# ArduinoMega.net
KiCad netlist of a schematic drawn in Altium Designer
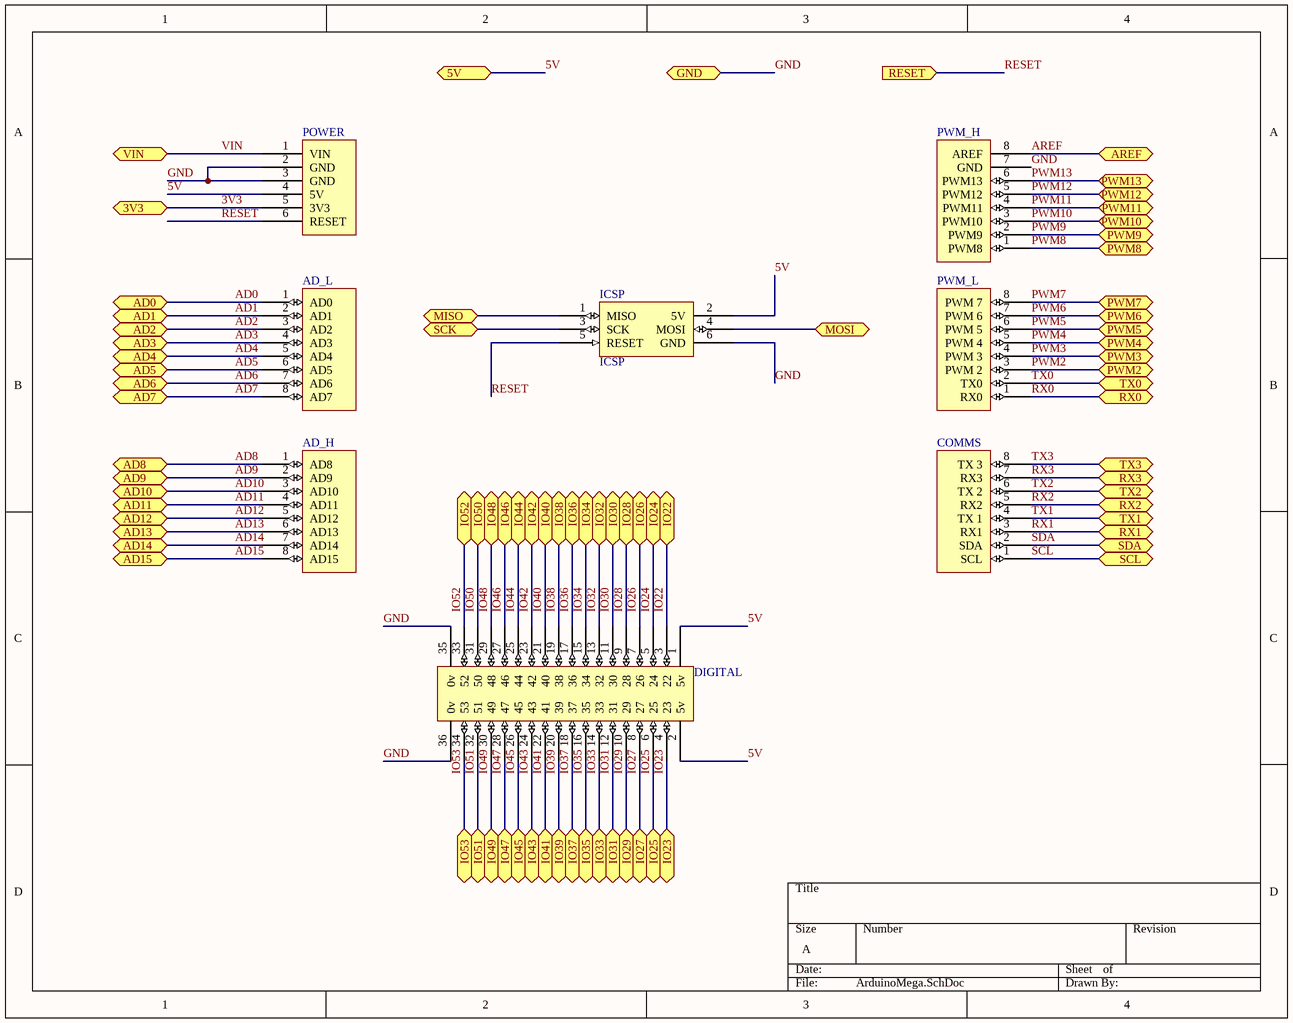
[diagram p0: ArduinoMega.SchDoc]

(export (version "E")
  (design (tool "Eeschema 10.0.6"))
  (components
    (comp (ref "AD_H") (value "AD_H") (footprint "HDR1X8") (libsource (lib "Header") (part "AD_H")))
    (comp (ref "AD_L") (value "AD_L") (footprint "HDR1X8") (libsource (lib "Header") (part "AD_L")))
    (comp (ref "COMMS")
      (value "Communication")
      (footprint "HDR1X8")
      (libsource (lib "Header") (part "Communication"))
    )
    (comp (ref "DIGITAL") (value "IO_36") (footprint "HDR2X18") (libsource (lib "Header") (part "IO_36")))
    (comp (ref "ICSP") (value "ICSP") (footprint "ICSP") (libsource (lib "Header") (part "ICSP")))
    (comp (ref "POWER") (value "POWER") (footprint "HDR1X6") (libsource (lib "Header") (part "POWER")))
    (comp (ref "PWM_H") (value "PWM_H") (footprint "HDR1X8") (libsource (lib "Header") (part "PWM_H")))
    (comp (ref "PWM_L") (value "PWM_L") (footprint "HDR1X8") (libsource (lib "Header") (part "PWM_L")))
  )
  (nets
    (net (code "1") (name "/3V3") (class "Default")
      (node (ref "POWER") (pin "5") (pinfunction "3V3_5") (pintype "power_in"))
    )
    (net (code "2") (name "/5V") (class "Default")
      (node (ref "DIGITAL") (pin "1") (pinfunction "5v_1") (pintype "power_in"))
      (node (ref "DIGITAL") (pin "2") (pinfunction "5v_2") (pintype "power_in"))
      (node (ref "ICSP") (pin "2") (pinfunction "5V_2") (pintype "power_in"))
      (node (ref "POWER") (pin "4") (pinfunction "5V_4") (pintype "power_in"))
    )
    (net (code "3") (name "/AD0") (class "Default")
      (node (ref "AD_L") (pin "1") (pinfunction "AD0_1") (pintype "bidirectional"))
    )
    (net (code "4") (name "/AD1") (class "Default")
      (node (ref "AD_L") (pin "2") (pinfunction "AD1_2") (pintype "bidirectional"))
    )
    (net (code "5") (name "/AD2") (class "Default")
      (node (ref "AD_L") (pin "3") (pinfunction "AD2_3") (pintype "bidirectional"))
    )
    (net (code "6") (name "/AD3") (class "Default")
      (node (ref "AD_L") (pin "4") (pinfunction "AD3_4") (pintype "bidirectional"))
    )
    (net (code "7") (name "/AD4") (class "Default")
      (node (ref "AD_L") (pin "5") (pinfunction "AD4_5") (pintype "bidirectional"))
    )
    (net (code "8") (name "/AD5") (class "Default")
      (node (ref "AD_L") (pin "6") (pinfunction "AD5_6") (pintype "bidirectional"))
    )
    (net (code "9") (name "/AD6") (class "Default")
      (node (ref "AD_L") (pin "7") (pinfunction "AD6_7") (pintype "bidirectional"))
    )
    (net (code "10") (name "/AD7") (class "Default")
      (node (ref "AD_L") (pin "8") (pinfunction "AD7_8") (pintype "bidirectional"))
    )
    (net (code "11") (name "/AD8") (class "Default")
      (node (ref "AD_H") (pin "1") (pinfunction "AD8_1") (pintype "bidirectional"))
    )
    (net (code "12") (name "/AD9") (class "Default")
      (node (ref "AD_H") (pin "2") (pinfunction "AD9_2") (pintype "bidirectional"))
    )
    (net (code "13") (name "/AD10") (class "Default")
      (node (ref "AD_H") (pin "3") (pinfunction "AD10_3") (pintype "bidirectional"))
    )
    (net (code "14") (name "/AD11") (class "Default")
      (node (ref "AD_H") (pin "4") (pinfunction "AD11_4") (pintype "bidirectional"))
    )
    (net (code "15") (name "/AD12") (class "Default")
      (node (ref "AD_H") (pin "5") (pinfunction "AD12_5") (pintype "bidirectional"))
    )
    (net (code "16") (name "/AD13") (class "Default")
      (node (ref "AD_H") (pin "6") (pinfunction "AD13_6") (pintype "bidirectional"))
    )
    (net (code "17") (name "/AD14") (class "Default")
      (node (ref "AD_H") (pin "7") (pinfunction "AD14_7") (pintype "bidirectional"))
    )
    (net (code "18") (name "/AD15") (class "Default")
      (node (ref "AD_H") (pin "8") (pinfunction "AD15_8") (pintype "bidirectional"))
    )
    (net (code "19") (name "/AREF") (class "Default")
      (node (ref "PWM_H") (pin "8") (pinfunction "AREF_8") (pintype "passive"))
    )
    (net (code "20") (name "/GND") (class "Default")
      (node (ref "DIGITAL") (pin "35") (pinfunction "0v_35") (pintype "power_in"))
      (node (ref "DIGITAL") (pin "36") (pinfunction "0v_36") (pintype "power_in"))
      (node (ref "ICSP") (pin "6") (pinfunction "GND_6") (pintype "power_in"))
      (node (ref "POWER") (pin "2") (pinfunction "GND_2") (pintype "power_in"))
      (node (ref "POWER") (pin "3") (pinfunction "GND_3") (pintype "power_in"))
      (node (ref "PWM_H") (pin "7") (pinfunction "GND_7") (pintype "power_in"))
    )
    (net (code "21") (name "/IO22") (class "Default")
      (node (ref "DIGITAL") (pin "3") (pinfunction "22_3") (pintype "bidirectional"))
    )
    (net (code "22") (name "/IO23") (class "Default")
      (node (ref "DIGITAL") (pin "4") (pinfunction "23_4") (pintype "bidirectional"))
    )
    (net (code "23") (name "/IO24") (class "Default")
      (node (ref "DIGITAL") (pin "5") (pinfunction "24_5") (pintype "bidirectional"))
    )
    (net (code "24") (name "/IO25") (class "Default")
      (node (ref "DIGITAL") (pin "6") (pinfunction "25_6") (pintype "bidirectional"))
    )
    (net (code "25") (name "/IO26") (class "Default")
      (node (ref "DIGITAL") (pin "7") (pinfunction "26_7") (pintype "bidirectional"))
    )
    (net (code "26") (name "/IO27") (class "Default")
      (node (ref "DIGITAL") (pin "8") (pinfunction "27_8") (pintype "bidirectional"))
    )
    (net (code "27") (name "/IO28") (class "Default")
      (node (ref "DIGITAL") (pin "9") (pinfunction "28_9") (pintype "bidirectional"))
    )
    (net (code "28") (name "/IO29") (class "Default")
      (node (ref "DIGITAL") (pin "10") (pinfunction "29_10") (pintype "bidirectional"))
    )
    (net (code "29") (name "/IO30") (class "Default")
      (node (ref "DIGITAL") (pin "11") (pinfunction "30_11") (pintype "bidirectional"))
    )
    (net (code "30") (name "/IO31") (class "Default")
      (node (ref "DIGITAL") (pin "12") (pinfunction "31_12") (pintype "bidirectional"))
    )
    (net (code "31") (name "/IO32") (class "Default")
      (node (ref "DIGITAL") (pin "13") (pinfunction "32_13") (pintype "bidirectional"))
    )
    (net (code "32") (name "/IO33") (class "Default")
      (node (ref "DIGITAL") (pin "14") (pinfunction "33_14") (pintype "bidirectional"))
    )
    (net (code "33") (name "/IO34") (class "Default")
      (node (ref "DIGITAL") (pin "15") (pinfunction "34_15") (pintype "bidirectional"))
    )
    (net (code "34") (name "/IO35") (class "Default")
      (node (ref "DIGITAL") (pin "16") (pinfunction "35_16") (pintype "bidirectional"))
    )
    (net (code "35") (name "/IO36") (class "Default")
      (node (ref "DIGITAL") (pin "17") (pinfunction "36_17") (pintype "bidirectional"))
    )
    (net (code "36") (name "/IO37") (class "Default")
      (node (ref "DIGITAL") (pin "18") (pinfunction "37_18") (pintype "bidirectional"))
    )
    (net (code "37") (name "/IO38") (class "Default")
      (node (ref "DIGITAL") (pin "19") (pinfunction "38_19") (pintype "bidirectional"))
    )
    (net (code "38") (name "/IO39") (class "Default")
      (node (ref "DIGITAL") (pin "20") (pinfunction "39_20") (pintype "bidirectional"))
    )
    (net (code "39") (name "/IO40") (class "Default")
      (node (ref "DIGITAL") (pin "21") (pinfunction "40_21") (pintype "bidirectional"))
    )
    (net (code "40") (name "/IO41") (class "Default")
      (node (ref "DIGITAL") (pin "22") (pinfunction "41_22") (pintype "bidirectional"))
    )
    (net (code "41") (name "/IO42") (class "Default")
      (node (ref "DIGITAL") (pin "23") (pinfunction "42_23") (pintype "bidirectional"))
    )
    (net (code "42") (name "/IO43") (class "Default")
      (node (ref "DIGITAL") (pin "24") (pinfunction "43_24") (pintype "bidirectional"))
    )
    (net (code "43") (name "/IO44") (class "Default")
      (node (ref "DIGITAL") (pin "25") (pinfunction "44_25") (pintype "bidirectional"))
    )
    (net (code "44") (name "/IO45") (class "Default")
      (node (ref "DIGITAL") (pin "26") (pinfunction "45_26") (pintype "bidirectional"))
    )
    (net (code "45") (name "/IO46") (class "Default")
      (node (ref "DIGITAL") (pin "27") (pinfunction "46_27") (pintype "bidirectional"))
    )
    (net (code "46") (name "/IO47") (class "Default")
      (node (ref "DIGITAL") (pin "28") (pinfunction "47_28") (pintype "bidirectional"))
    )
    (net (code "47") (name "/IO48") (class "Default")
      (node (ref "DIGITAL") (pin "29") (pinfunction "48_29") (pintype "bidirectional"))
    )
    (net (code "48") (name "/IO49") (class "Default")
      (node (ref "DIGITAL") (pin "30") (pinfunction "49_30") (pintype "bidirectional"))
    )
    (net (code "49") (name "/IO50") (class "Default")
      (node (ref "DIGITAL") (pin "31") (pinfunction "50_31") (pintype "bidirectional"))
    )
    (net (code "50") (name "/IO51") (class "Default")
      (node (ref "DIGITAL") (pin "32") (pinfunction "51_32") (pintype "bidirectional"))
    )
    (net (code "51") (name "/IO52") (class "Default")
      (node (ref "DIGITAL") (pin "33") (pinfunction "52_33") (pintype "bidirectional"))
    )
    (net (code "52") (name "/IO53") (class "Default")
      (node (ref "DIGITAL") (pin "34") (pinfunction "53_34") (pintype "bidirectional"))
    )
    (net (code "53") (name "/MISO") (class "Default")
      (node (ref "ICSP") (pin "1") (pinfunction "MISO_1") (pintype "bidirectional"))
    )
    (net (code "54") (name "/MOSI") (class "Default")
      (node (ref "ICSP") (pin "4") (pinfunction "MOSI_4") (pintype "bidirectional"))
    )
    (net (code "55") (name "/PWM2") (class "Default")
      (node (ref "PWM_L") (pin "3") (pinfunction "PWM_2_3") (pintype "bidirectional"))
    )
    (net (code "56") (name "/PWM3") (class "Default")
      (node (ref "PWM_L") (pin "4") (pinfunction "PWM_3_4") (pintype "bidirectional"))
    )
    (net (code "57") (name "/PWM4") (class "Default")
      (node (ref "PWM_L") (pin "5") (pinfunction "PWM_4_5") (pintype "bidirectional"))
    )
    (net (code "58") (name "/PWM5") (class "Default")
      (node (ref "PWM_L") (pin "6") (pinfunction "PWM_5_6") (pintype "bidirectional"))
    )
    (net (code "59") (name "/PWM6") (class "Default")
      (node (ref "PWM_L") (pin "7") (pinfunction "PWM_6_7") (pintype "bidirectional"))
    )
    (net (code "60") (name "/PWM7") (class "Default")
      (node (ref "PWM_L") (pin "8") (pinfunction "PWM_7_8") (pintype "bidirectional"))
    )
    (net (code "61") (name "/PWM8") (class "Default")
      (node (ref "PWM_H") (pin "1") (pinfunction "PWM8_1") (pintype "bidirectional"))
    )
    (net (code "62") (name "/PWM9") (class "Default")
      (node (ref "PWM_H") (pin "2") (pinfunction "PWM9_2") (pintype "bidirectional"))
    )
    (net (code "63") (name "/PWM10") (class "Default")
      (node (ref "PWM_H") (pin "3") (pinfunction "PWM10_3") (pintype "bidirectional"))
    )
    (net (code "64") (name "/PWM11") (class "Default")
      (node (ref "PWM_H") (pin "4") (pinfunction "PWM11_4") (pintype "bidirectional"))
    )
    (net (code "65") (name "/PWM12") (class "Default")
      (node (ref "PWM_H") (pin "5") (pinfunction "PWM12_5") (pintype "bidirectional"))
    )
    (net (code "66") (name "/PWM13") (class "Default")
      (node (ref "PWM_H") (pin "6") (pinfunction "PWM13_6") (pintype "bidirectional"))
    )
    (net (code "67") (name "/RESET") (class "Default")
      (node (ref "ICSP") (pin "5") (pinfunction "RESET_5") (pintype "input"))
      (node (ref "POWER") (pin "6") (pinfunction "RESET_6") (pintype "passive"))
    )
    (net (code "68") (name "/RX0") (class "Default")
      (node (ref "PWM_L") (pin "1") (pinfunction "RX0_1") (pintype "bidirectional"))
    )
    (net (code "69") (name "/RX1") (class "Default")
      (node (ref "COMMS") (pin "3") (pinfunction "RX1_3") (pintype "bidirectional"))
    )
    (net (code "70") (name "/RX2") (class "Default")
      (node (ref "COMMS") (pin "5") (pinfunction "RX2_5") (pintype "bidirectional"))
    )
    (net (code "71") (name "/RX3") (class "Default")
      (node (ref "COMMS") (pin "7") (pinfunction "RX3_7") (pintype "bidirectional"))
    )
    (net (code "72") (name "/SCK") (class "Default")
      (node (ref "ICSP") (pin "3") (pinfunction "SCK_3") (pintype "bidirectional"))
    )
    (net (code "73") (name "/SCL") (class "Default")
      (node (ref "COMMS") (pin "1") (pinfunction "SCL_1") (pintype "bidirectional"))
    )
    (net (code "74") (name "/SDA") (class "Default")
      (node (ref "COMMS") (pin "2") (pinfunction "SDA_2") (pintype "bidirectional"))
    )
    (net (code "75") (name "/TX0") (class "Default")
      (node (ref "PWM_L") (pin "2") (pinfunction "TX0_2") (pintype "bidirectional"))
    )
    (net (code "76") (name "/TX1") (class "Default")
      (node (ref "COMMS") (pin "4") (pinfunction "TX_1_4") (pintype "bidirectional"))
    )
    (net (code "77") (name "/TX2") (class "Default")
      (node (ref "COMMS") (pin "6") (pinfunction "TX_2_6") (pintype "bidirectional"))
    )
    (net (code "78") (name "/TX3") (class "Default")
      (node (ref "COMMS") (pin "8") (pinfunction "TX_3_8") (pintype "bidirectional"))
    )
    (net (code "79") (name "/VIN") (class "Default")
      (node (ref "POWER") (pin "1") (pinfunction "VIN_1") (pintype "power_in"))
    )
  )
)
